# MainBoard.net
KiCad netlist of a schematic drawn in EAGLE
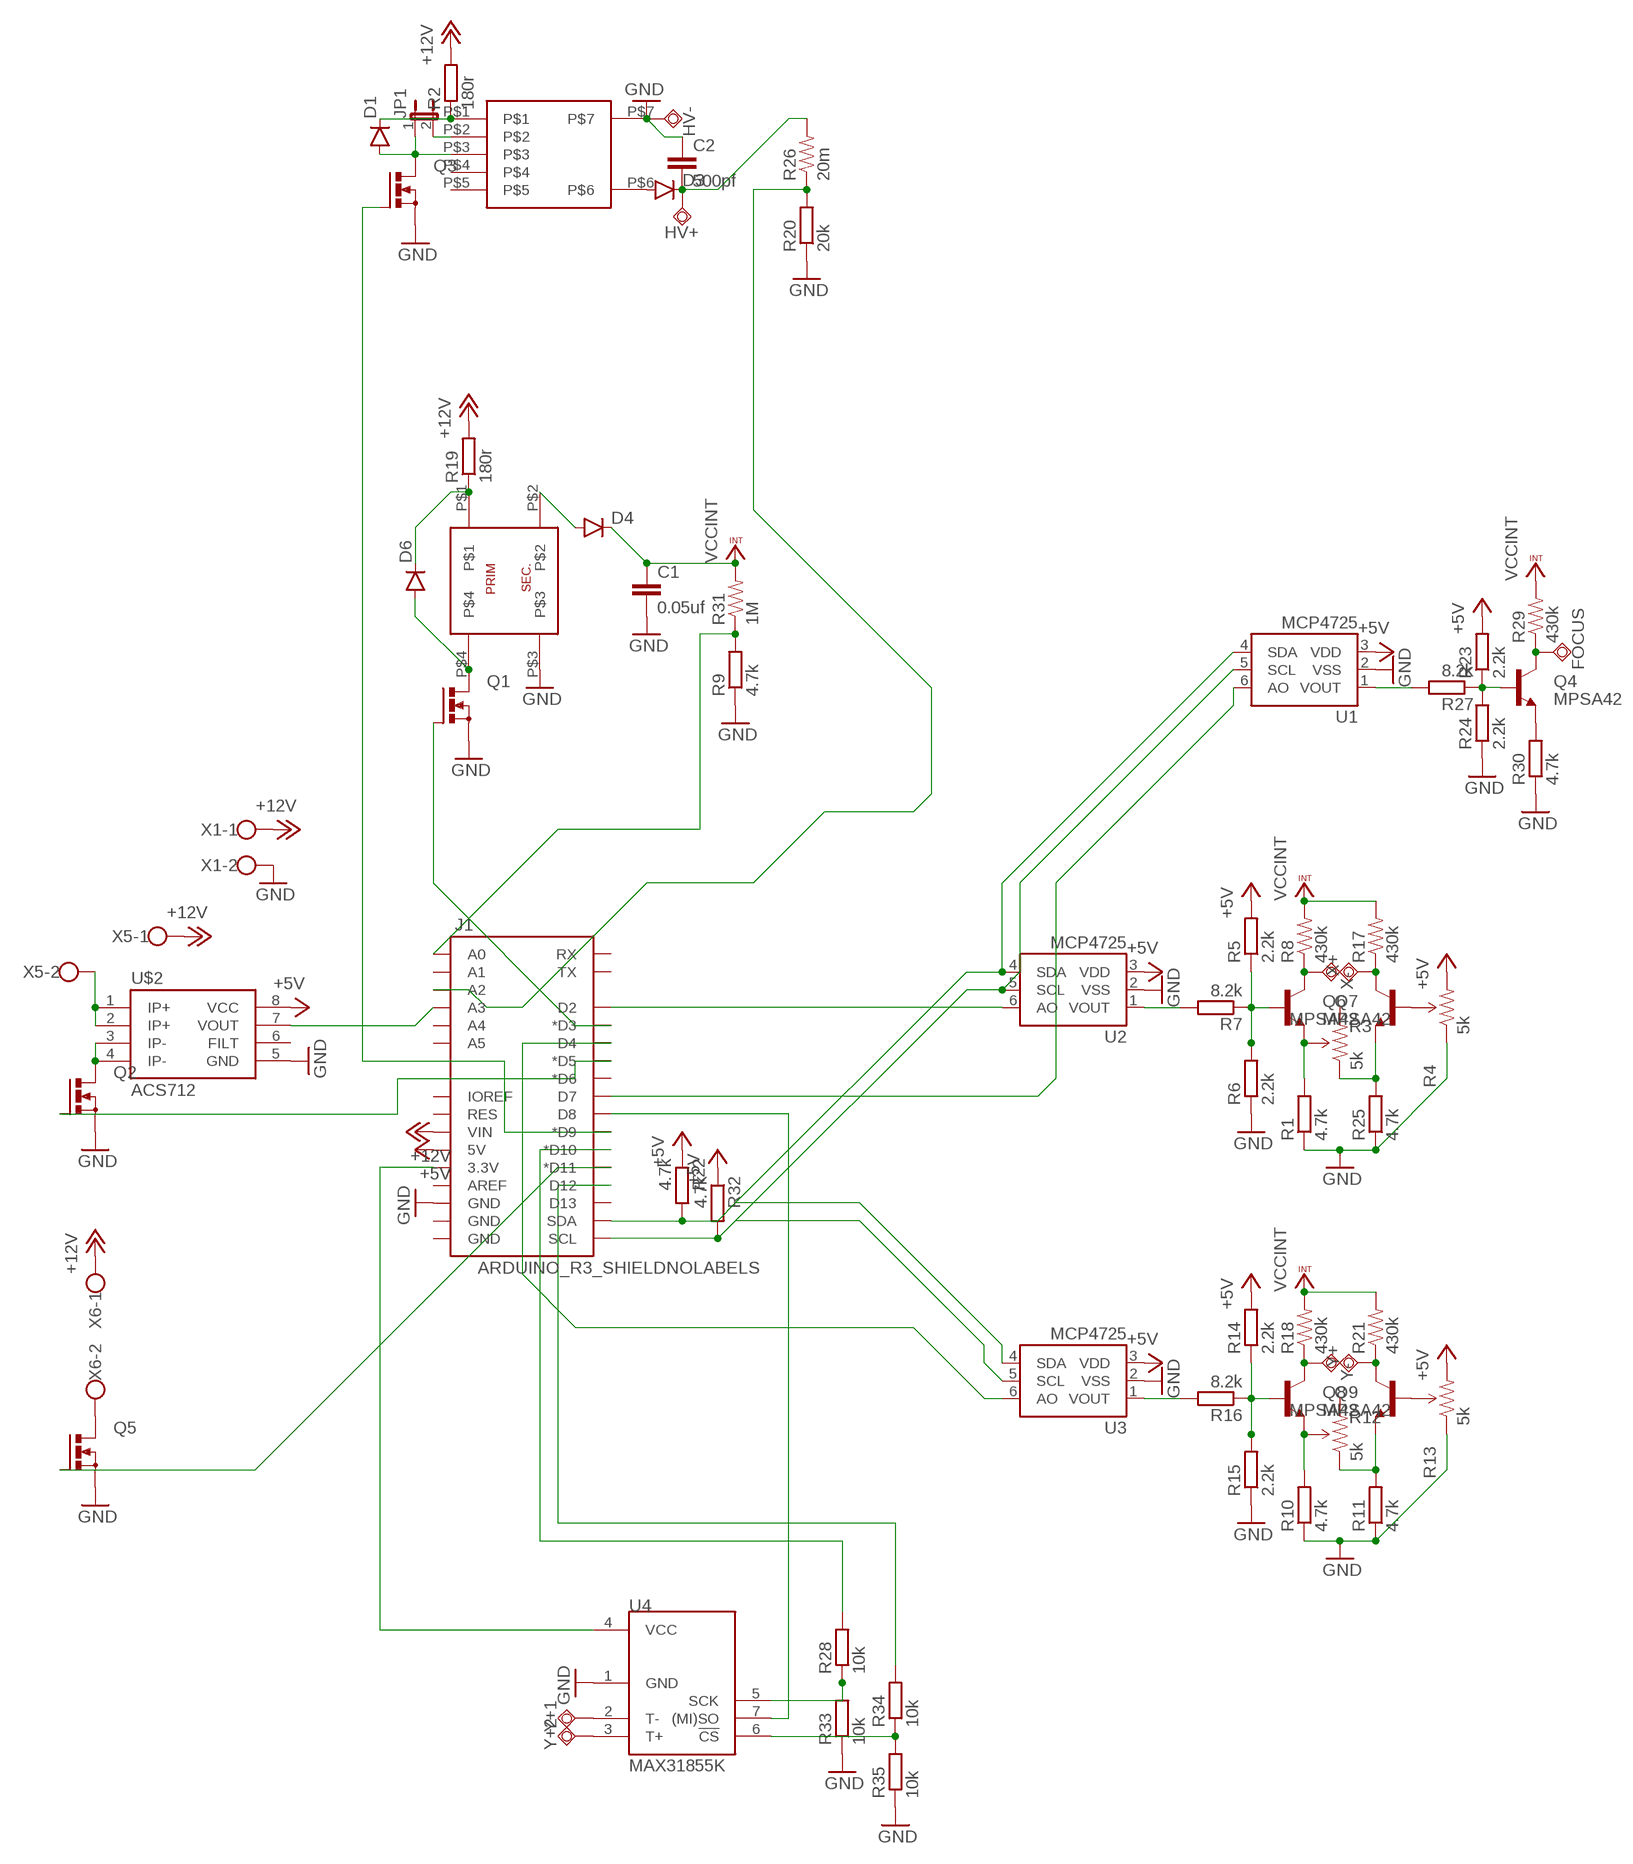
[diagram p0: schematic, sheet 1]

(export (version "E")
  (design (tool "Eeschema 10.0.6"))
  (components
    (comp (ref "C1")
      (value "0.05uf")
      (footprint "eagle-import:C1206")
      (libsource (lib "eagle-import") (part "CC1206"))
    )
    (comp (ref "C2")
      (value "500pf")
      (footprint "eagle-import:C1206")
      (libsource (lib "eagle-import") (part "CC1206"))
    )
    (comp (ref "D1")
      (value "DIODESOD123")
      (footprint "eagle-import:SOD-123")
      (libsource (lib "eagle-import") (part "DIODESOD123"))
    )
    (comp (ref "D3")
      (value "DIODEPTH")
      (footprint "eagle-import:DIODE-1N4001")
      (libsource (lib "eagle-import") (part "DIODEPTH"))
    )
    (comp (ref "D4")
      (value "DIODESOD123")
      (footprint "eagle-import:SOD-123")
      (libsource (lib "eagle-import") (part "DIODESOD123"))
    )
    (comp (ref "D6")
      (value "DIODESOD123")
      (footprint "eagle-import:SOD-123")
      (libsource (lib "eagle-import") (part "DIODESOD123"))
    )
    (comp (ref "FOCUS")
      (value "FOCUS")
      (footprint "eagle-import:P1-13")
      (libsource (lib "eagle-import") (part "TPSQPAD1-13"))
    )
    (comp (ref "HV+")
      (value "TPSQPAD1-13")
      (footprint "eagle-import:P1-13")
      (libsource (lib "eagle-import") (part "TPSQPAD1-13"))
    )
    (comp (ref "HV-")
      (value "TPSQPAD1-13")
      (footprint "eagle-import:P1-13")
      (libsource (lib "eagle-import") (part "TPSQPAD1-13"))
    )
    (comp (ref "J1")
      (value "ARDUINO_R3_SHIELDNOLABELS")
      (footprint "eagle-import:UNO_R3_SHIELD_NOLABELS")
      (libsource (lib "eagle-import") (part "ARDUINO_R3_SHIELDNOLABELS"))
    )
    (comp (ref "JP1")
      (value "JUMPER-2SMD-NO")
      (footprint "eagle-import:SJ_2S-NO")
      (libsource (lib "eagle-import") (part "JUMPER-2SMD-NO"))
    )
    (comp (ref "Q1")
      (value "N-MOSFET-SO8S")
      (footprint "eagle-import:SO-08")
      (libsource (lib "eagle-import") (part "N-MOSFET-SO8S"))
    )
    (comp (ref "Q2")
      (value "N-MOSFET-SO8S")
      (footprint "eagle-import:SO-08")
      (libsource (lib "eagle-import") (part "N-MOSFET-SO8S"))
    )
    (comp (ref "Q3")
      (value "N-MOSFET-SO8S")
      (footprint "eagle-import:SO-08")
      (libsource (lib "eagle-import") (part "N-MOSFET-SO8S"))
    )
    (comp (ref "Q4")
      (value "MPSA42")
      (footprint "eagle-import:SOT23-3")
      (libsource (lib "eagle-import") (part "TRANSISTOR_NPNMPSA42"))
    )
    (comp (ref "Q5")
      (value "N-MOSFET-SO8S")
      (footprint "eagle-import:SO-08")
      (libsource (lib "eagle-import") (part "N-MOSFET-SO8S"))
    )
    (comp (ref "Q6")
      (value "MPSA42")
      (footprint "eagle-import:SOT23-3")
      (libsource (lib "eagle-import") (part "TRANSISTOR_NPNMPSA42"))
    )
    (comp (ref "Q7")
      (value "MPSA42")
      (footprint "eagle-import:SOT23-3")
      (libsource (lib "eagle-import") (part "TRANSISTOR_NPNMPSA42"))
    )
    (comp (ref "Q8")
      (value "MPSA42")
      (footprint "eagle-import:SOT23-3")
      (libsource (lib "eagle-import") (part "TRANSISTOR_NPNMPSA42"))
    )
    (comp (ref "Q9")
      (value "MPSA42")
      (footprint "eagle-import:SOT23-3")
      (libsource (lib "eagle-import") (part "TRANSISTOR_NPNMPSA42"))
    )
    (comp (ref "R1")
      (value "4.7k")
      (footprint "eagle-import:R0603")
      (libsource (lib "eagle-import") (part "R-EU_R0603"))
    )
    (comp (ref "R2")
      (value "180r")
      (footprint "eagle-import:R0603")
      (libsource (lib "eagle-import") (part "R-EU_R0603"))
    )
    (comp (ref "R3")
      (value "5k")
      (footprint "eagle-import:TRIMPOT_PTH_S3_LOCK")
      (libsource (lib "eagle-import") (part "TRIMPOTTRIMPOT_PTH_S3_LOCK"))
    )
    (comp (ref "R4")
      (value "5k")
      (footprint "eagle-import:TRIMPOT_PTH_S3_LOCK")
      (libsource (lib "eagle-import") (part "TRIMPOTTRIMPOT_PTH_S3_LOCK"))
    )
    (comp (ref "R5")
      (value "2.2k")
      (footprint "eagle-import:R0603")
      (libsource (lib "eagle-import") (part "R-EU_R0603"))
    )
    (comp (ref "R6")
      (value "2.2k")
      (footprint "eagle-import:R0603")
      (libsource (lib "eagle-import") (part "R-EU_R0603"))
    )
    (comp (ref "R7")
      (value "8.2k")
      (footprint "eagle-import:R0603")
      (libsource (lib "eagle-import") (part "R-EU_R0603"))
    )
    (comp (ref "R8")
      (value "430k")
      (footprint "eagle-import:1206")
      (libsource (lib "eagle-import") (part "RESISTOR1206"))
    )
    (comp (ref "R9")
      (value "4.7k")
      (footprint "eagle-import:R0603")
      (libsource (lib "eagle-import") (part "R-EU_R0603"))
    )
    (comp (ref "R10")
      (value "4.7k")
      (footprint "eagle-import:R0603")
      (libsource (lib "eagle-import") (part "R-EU_R0603"))
    )
    (comp (ref "R11")
      (value "4.7k")
      (footprint "eagle-import:R0603")
      (libsource (lib "eagle-import") (part "R-EU_R0603"))
    )
    (comp (ref "R12")
      (value "5k")
      (footprint "eagle-import:TRIMPOT_PTH_S3_LOCK")
      (libsource (lib "eagle-import") (part "TRIMPOTTRIMPOT_PTH_S3_LOCK"))
    )
    (comp (ref "R13")
      (value "5k")
      (footprint "eagle-import:TRIMPOT_PTH_S3_LOCK")
      (libsource (lib "eagle-import") (part "TRIMPOTTRIMPOT_PTH_S3_LOCK"))
    )
    (comp (ref "R14")
      (value "2.2k")
      (footprint "eagle-import:R0603")
      (libsource (lib "eagle-import") (part "R-EU_R0603"))
    )
    (comp (ref "R15")
      (value "2.2k")
      (footprint "eagle-import:R0603")
      (libsource (lib "eagle-import") (part "R-EU_R0603"))
    )
    (comp (ref "R16")
      (value "8.2k")
      (footprint "eagle-import:R0603")
      (libsource (lib "eagle-import") (part "R-EU_R0603"))
    )
    (comp (ref "R17")
      (value "430k")
      (footprint "eagle-import:1206")
      (libsource (lib "eagle-import") (part "RESISTOR1206"))
    )
    (comp (ref "R18")
      (value "430k")
      (footprint "eagle-import:1206")
      (libsource (lib "eagle-import") (part "RESISTOR1206"))
    )
    (comp (ref "R19")
      (value "180r")
      (footprint "eagle-import:R0603")
      (libsource (lib "eagle-import") (part "R-EU_R0603"))
    )
    (comp (ref "R20")
      (value "20k")
      (footprint "eagle-import:R0603")
      (libsource (lib "eagle-import") (part "R-EU_R0603"))
    )
    (comp (ref "R21")
      (value "430k")
      (footprint "eagle-import:1206")
      (libsource (lib "eagle-import") (part "RESISTOR1206"))
    )
    (comp (ref "R22")
      (value "4.7k")
      (footprint "eagle-import:R0603")
      (libsource (lib "eagle-import") (part "R-EU_R0603"))
    )
    (comp (ref "R23")
      (value "2.2k")
      (footprint "eagle-import:R0603")
      (libsource (lib "eagle-import") (part "R-EU_R0603"))
    )
    (comp (ref "R24")
      (value "2.2k")
      (footprint "eagle-import:R0603")
      (libsource (lib "eagle-import") (part "R-EU_R0603"))
    )
    (comp (ref "R25")
      (value "4.7k")
      (footprint "eagle-import:R0603")
      (libsource (lib "eagle-import") (part "R-EU_R0603"))
    )
    (comp (ref "R26")
      (value "20m")
      (footprint "eagle-import:AXIAL-0.4")
      (libsource (lib "eagle-import") (part "RESISTORPTH-1/4W"))
    )
    (comp (ref "R27")
      (value "8.2k")
      (footprint "eagle-import:R0603")
      (libsource (lib "eagle-import") (part "R-EU_R0603"))
    )
    (comp (ref "R28")
      (value "10k")
      (footprint "eagle-import:R0603")
      (libsource (lib "eagle-import") (part "R-EU_R0603"))
    )
    (comp (ref "R29")
      (value "430k")
      (footprint "eagle-import:1206")
      (libsource (lib "eagle-import") (part "RESISTOR1206"))
    )
    (comp (ref "R30")
      (value "4.7k")
      (footprint "eagle-import:R0603")
      (libsource (lib "eagle-import") (part "R-EU_R0603"))
    )
    (comp (ref "R31")
      (value "1M")
      (footprint "eagle-import:1206")
      (libsource (lib "eagle-import") (part "RESISTOR1206"))
    )
    (comp (ref "R32")
      (value "4.7k")
      (footprint "eagle-import:R0603")
      (libsource (lib "eagle-import") (part "R-EU_R0603"))
    )
    (comp (ref "R33")
      (value "10k")
      (footprint "eagle-import:R0603")
      (libsource (lib "eagle-import") (part "R-EU_R0603"))
    )
    (comp (ref "R34")
      (value "10k")
      (footprint "eagle-import:R0603")
      (libsource (lib "eagle-import") (part "R-EU_R0603"))
    )
    (comp (ref "R35")
      (value "10k")
      (footprint "eagle-import:R0603")
      (libsource (lib "eagle-import") (part "R-EU_R0603"))
    )
    (comp (ref "U$1")
      (value "ATB")
      (footprint "eagle-import:ATB3225")
      (libsource (lib "eagle-import") (part "ATB"))
    )
    (comp (ref "U$2")
      (value "ACS712")
      (footprint "eagle-import:SO08")
      (libsource (lib "eagle-import") (part "ACS712"))
    )
    (comp (ref "U$3")
      (value "CTX")
      (footprint "eagle-import:CTX")
      (libsource (lib "eagle-import") (part "CTX"))
    )
    (comp (ref "U1")
      (value "MCP4725")
      (footprint "eagle-import:SOT23-6")
      (libsource (lib "eagle-import") (part "MCP4725SOT-23"))
    )
    (comp (ref "U2")
      (value "MCP4725")
      (footprint "eagle-import:SOT23-6")
      (libsource (lib "eagle-import") (part "MCP4725SOT-23"))
    )
    (comp (ref "U3")
      (value "MCP4725")
      (footprint "eagle-import:SOT23-6")
      (libsource (lib "eagle-import") (part "MCP4725SOT-23"))
    )
    (comp (ref "U4")
      (value "MAX31855K")
      (footprint "eagle-import:SOIC8")
      (libsource (lib "eagle-import") (part "MAX31855K"))
    )
    (comp (ref "X+")
      (value "TPSQPAD1-13")
      (footprint "eagle-import:P1-13")
      (libsource (lib "eagle-import") (part "TPSQPAD1-13"))
    )
    (comp (ref "X-")
      (value "TPSQPAD1-13")
      (footprint "eagle-import:P1-13")
      (libsource (lib "eagle-import") (part "TPSQPAD1-13"))
    )
    (comp (ref "X1")
      (value "W237-102")
      (footprint "eagle-import:W237-102")
      (fields (field (name "MPN") "237-102"))
      (libsource (lib "eagle-import") (part "W237-102"))
    )
    (comp (ref "X5")
      (value "W237-102")
      (footprint "eagle-import:W237-102")
      (fields (field (name "MPN") "237-102"))
      (libsource (lib "eagle-import") (part "W237-102"))
    )
    (comp (ref "X6")
      (value "W237-102")
      (footprint "eagle-import:W237-102")
      (fields (field (name "MPN") "237-102"))
      (libsource (lib "eagle-import") (part "W237-102"))
    )
    (comp (ref "Y+")
      (value "TPSQPAD1-13")
      (footprint "eagle-import:P1-13")
      (libsource (lib "eagle-import") (part "TPSQPAD1-13"))
    )
    (comp (ref "Y+1")
      (value "TPSQPAD1-13")
      (footprint "eagle-import:P1-13")
      (libsource (lib "eagle-import") (part "TPSQPAD1-13"))
    )
    (comp (ref "Y+2")
      (value "TPSQPAD1-13")
      (footprint "eagle-import:P1-13")
      (libsource (lib "eagle-import") (part "TPSQPAD1-13"))
    )
    (comp (ref "Y-")
      (value "TPSQPAD1-13")
      (footprint "eagle-import:P1-13")
      (libsource (lib "eagle-import") (part "TPSQPAD1-13"))
    )
  )
  (nets
    (net (code "1") (name "+5V") (class "Default")
      (node (ref "J1") (pin "5V") (pinfunction "5V_5V") (pintype "bidirectional"))
      (node (ref "R13") (pin "3") (pinfunction "CW_3") (pintype "passive"))
      (node (ref "R14") (pin "2") (pinfunction "2_2") (pintype "passive"))
      (node (ref "R22") (pin "1") (pinfunction "1_1") (pintype "passive"))
      (node (ref "R23") (pin "2") (pinfunction "2_2") (pintype "passive"))
      (node (ref "R32") (pin "1") (pinfunction "1_1") (pintype "passive"))
      (node (ref "R4") (pin "3") (pinfunction "CW_3") (pintype "passive"))
      (node (ref "R5") (pin "2") (pinfunction "2_2") (pintype "passive"))
      (node (ref "U$2") (pin "8") (pinfunction "VCC_8") (pintype "bidirectional"))
      (node (ref "U1") (pin "3") (pinfunction "VDD_3") (pintype "bidirectional"))
      (node (ref "U2") (pin "3") (pinfunction "VDD_3") (pintype "bidirectional"))
      (node (ref "U3") (pin "3") (pinfunction "VDD_3") (pintype "bidirectional"))
    )
    (net (code "2") (name "+12V") (class "Default")
      (node (ref "J1") (pin "VIN") (pinfunction "VIN_VIN") (pintype "bidirectional"))
      (node (ref "R19") (pin "2") (pinfunction "2_2") (pintype "passive"))
      (node (ref "R2") (pin "2") (pinfunction "2_2") (pintype "passive"))
      (node (ref "X1") (pin "1") (pinfunction "KL_1") (pintype "passive"))
      (node (ref "X5") (pin "1") (pinfunction "KL_1") (pintype "passive"))
      (node (ref "X6") (pin "1") (pinfunction "KL_1") (pintype "passive"))
    )
    (net (code "3") (name "GND") (class "Default")
      (node (ref "C1") (pin "2") (pinfunction "2_2") (pintype "passive"))
      (node (ref "C2") (pin "1") (pinfunction "1_1") (pintype "passive"))
      (node (ref "HV-") (pin "TP") (pinfunction "TP_TP") (pintype "input"))
      (node (ref "J1") (pin "GND@2") (pinfunction "GND_GND@2") (pintype "bidirectional"))
      (node (ref "Q1") (pin "1") (pinfunction "S_1") (pintype "passive"))
      (node (ref "Q1") (pin "2") (pinfunction "S_2") (pintype "passive"))
      (node (ref "Q1") (pin "3") (pinfunction "S_3") (pintype "passive"))
      (node (ref "Q2") (pin "1") (pinfunction "S_1") (pintype "passive"))
      (node (ref "Q2") (pin "2") (pinfunction "S_2") (pintype "passive"))
      (node (ref "Q2") (pin "3") (pinfunction "S_3") (pintype "passive"))
      (node (ref "Q3") (pin "1") (pinfunction "S_1") (pintype "passive"))
      (node (ref "Q3") (pin "2") (pinfunction "S_2") (pintype "passive"))
      (node (ref "Q3") (pin "3") (pinfunction "S_3") (pintype "passive"))
      (node (ref "Q5") (pin "1") (pinfunction "S_1") (pintype "passive"))
      (node (ref "Q5") (pin "2") (pinfunction "S_2") (pintype "passive"))
      (node (ref "Q5") (pin "3") (pinfunction "S_3") (pintype "passive"))
      (node (ref "R1") (pin "1") (pinfunction "1_1") (pintype "passive"))
      (node (ref "R10") (pin "1") (pinfunction "1_1") (pintype "passive"))
      (node (ref "R11") (pin "1") (pinfunction "1_1") (pintype "passive"))
      (node (ref "R13") (pin "1") (pinfunction "CCW_1") (pintype "passive"))
      (node (ref "R15") (pin "1") (pinfunction "1_1") (pintype "passive"))
      (node (ref "R20") (pin "1") (pinfunction "1_1") (pintype "passive"))
      (node (ref "R24") (pin "1") (pinfunction "1_1") (pintype "passive"))
      (node (ref "R25") (pin "1") (pinfunction "1_1") (pintype "passive"))
      (node (ref "R30") (pin "1") (pinfunction "1_1") (pintype "passive"))
      (node (ref "R33") (pin "1") (pinfunction "1_1") (pintype "passive"))
      (node (ref "R35") (pin "1") (pinfunction "1_1") (pintype "passive"))
      (node (ref "R4") (pin "1") (pinfunction "CCW_1") (pintype "passive"))
      (node (ref "R6") (pin "1") (pinfunction "1_1") (pintype "passive"))
      (node (ref "R9") (pin "1") (pinfunction "1_1") (pintype "passive"))
      (node (ref "U$1") (pin "P$3") (pinfunction "P$3_P$3") (pintype "bidirectional"))
      (node (ref "U$2") (pin "5") (pinfunction "GND_5") (pintype "bidirectional"))
      (node (ref "U$3") (pin "P$7") (pinfunction "P$7_P$7") (pintype "bidirectional"))
      (node (ref "U1") (pin "2") (pinfunction "VSS_2") (pintype "bidirectional"))
      (node (ref "U2") (pin "2") (pinfunction "VSS_2") (pintype "bidirectional"))
      (node (ref "U3") (pin "2") (pinfunction "VSS_2") (pintype "bidirectional"))
      (node (ref "U4") (pin "1") (pinfunction "GND_1") (pintype "bidirectional"))
      (node (ref "X1") (pin "2") (pinfunction "KL_2") (pintype "passive"))
    )
    (net (code "4") (name "Net-(D1-PadA)") (class "Default")
      (node (ref "D1") (pin "A") (pinfunction "A_A") (pintype "passive"))
      (node (ref "JP1") (pin "1") (pinfunction "1_1") (pintype "passive"))
      (node (ref "Q3") (pin "5") (pinfunction "D_5") (pintype "passive"))
      (node (ref "Q3") (pin "6") (pinfunction "D_6") (pintype "passive"))
      (node (ref "Q3") (pin "7") (pinfunction "D_7") (pintype "passive"))
      (node (ref "Q3") (pin "8") (pinfunction "D_8") (pintype "passive"))
      (node (ref "U$3") (pin "P$3") (pinfunction "P$3_P$3") (pintype "bidirectional"))
    )
    (net (code "5") (name "Net-(D1-PadC)") (class "Default")
      (node (ref "D1") (pin "C") (pinfunction "C_C") (pintype "passive"))
      (node (ref "R2") (pin "1") (pinfunction "1_1") (pintype "passive"))
      (node (ref "U$3") (pin "P$1") (pinfunction "P$1_P$1") (pintype "bidirectional"))
    )
    (net (code "6") (name "Net-(D3-PadA)") (class "Default")
      (node (ref "D3") (pin "A") (pinfunction "A_A") (pintype "passive"))
      (node (ref "U$3") (pin "P$6") (pinfunction "P$6_P$6") (pintype "bidirectional"))
    )
    (net (code "7") (name "Net-(D4-PadA)") (class "Default")
      (node (ref "D4") (pin "A") (pinfunction "A_A") (pintype "passive"))
      (node (ref "U$1") (pin "P$2") (pinfunction "P$2_P$2") (pintype "bidirectional"))
    )
    (net (code "8") (name "Net-(D6-PadA)") (class "Default")
      (node (ref "D6") (pin "A") (pinfunction "A_A") (pintype "passive"))
      (node (ref "Q1") (pin "5") (pinfunction "D_5") (pintype "passive"))
      (node (ref "Q1") (pin "6") (pinfunction "D_6") (pintype "passive"))
      (node (ref "Q1") (pin "7") (pinfunction "D_7") (pintype "passive"))
      (node (ref "Q1") (pin "8") (pinfunction "D_8") (pintype "passive"))
      (node (ref "U$1") (pin "P$4") (pinfunction "P$4_P$4") (pintype "bidirectional"))
    )
    (net (code "9") (name "Net-(D6-PadC)") (class "Default")
      (node (ref "D6") (pin "C") (pinfunction "C_C") (pintype "passive"))
      (node (ref "R19") (pin "1") (pinfunction "1_1") (pintype "passive"))
      (node (ref "U$1") (pin "P$1") (pinfunction "P$1_P$1") (pintype "bidirectional"))
    )
    (net (code "10") (name "Net-(J1-*D3)") (class "Default")
      (node (ref "J1") (pin "D3") (pinfunction "*D3_D3") (pintype "bidirectional"))
      (node (ref "Q1") (pin "4") (pinfunction "G_4") (pintype "passive"))
    )
    (net (code "11") (name "Net-(J1-*D5)") (class "Default")
      (node (ref "J1") (pin "D5") (pinfunction "*D5_D5") (pintype "bidirectional"))
      (node (ref "Q2") (pin "4") (pinfunction "G_4") (pintype "passive"))
    )
    (net (code "12") (name "Net-(J1-*D9)") (class "Default")
      (node (ref "J1") (pin "D9") (pinfunction "*D9_D9") (pintype "bidirectional"))
      (node (ref "Q3") (pin "4") (pinfunction "G_4") (pintype "passive"))
    )
    (net (code "13") (name "Net-(J1-*D10)") (class "Default")
      (node (ref "J1") (pin "D10") (pinfunction "*D10_D10") (pintype "bidirectional"))
      (node (ref "R28") (pin "2") (pinfunction "2_2") (pintype "passive"))
    )
    (net (code "14") (name "Net-(J1-*D11)") (class "Default")
      (node (ref "J1") (pin "D11") (pinfunction "*D11_D11") (pintype "bidirectional"))
      (node (ref "Q5") (pin "4") (pinfunction "G_4") (pintype "passive"))
    )
    (net (code "15") (name "Net-(J1-PadA0)") (class "Default")
      (node (ref "J1") (pin "A0") (pinfunction "A0_A0") (pintype "bidirectional"))
      (node (ref "R31") (pin "1") (pinfunction "1_1") (pintype "passive"))
      (node (ref "R9") (pin "2") (pinfunction "2_2") (pintype "passive"))
    )
    (net (code "16") (name "Net-(J1-PadD12)") (class "Default")
      (node (ref "J1") (pin "D12") (pinfunction "D12_D12") (pintype "bidirectional"))
      (node (ref "R34") (pin "2") (pinfunction "2_2") (pintype "passive"))
    )
    (net (code "17") (name "Net-(JP1-Pad2)") (class "Default")
      (node (ref "JP1") (pin "2") (pinfunction "2_2") (pintype "passive"))
      (node (ref "U$3") (pin "P$2") (pinfunction "P$2_P$2") (pintype "bidirectional"))
    )
    (net (code "18") (name "Net-(Q2-D-Pad5)") (class "Default")
      (node (ref "Q2") (pin "5") (pinfunction "D_5") (pintype "passive"))
      (node (ref "Q2") (pin "6") (pinfunction "D_6") (pintype "passive"))
      (node (ref "Q2") (pin "7") (pinfunction "D_7") (pintype "passive"))
      (node (ref "Q2") (pin "8") (pinfunction "D_8") (pintype "passive"))
      (node (ref "U$2") (pin "3") (pinfunction "IP-_3") (pintype "bidirectional"))
      (node (ref "U$2") (pin "4") (pinfunction "IP-_4") (pintype "bidirectional"))
    )
    (net (code "19") (name "Net-(Q4-B)") (class "Default")
      (node (ref "Q4") (pin "1") (pinfunction "B_1") (pintype "passive"))
      (node (ref "R23") (pin "1") (pinfunction "1_1") (pintype "passive"))
      (node (ref "R24") (pin "2") (pinfunction "2_2") (pintype "passive"))
      (node (ref "R27") (pin "1") (pinfunction "1_1") (pintype "passive"))
    )
    (net (code "20") (name "Net-(Q4-C)") (class "Default")
      (node (ref "FOCUS") (pin "TP") (pinfunction "TP_TP") (pintype "input"))
      (node (ref "Q4") (pin "3") (pinfunction "C_3") (pintype "passive"))
      (node (ref "R29") (pin "1") (pinfunction "1_1") (pintype "passive"))
    )
    (net (code "21") (name "Net-(Q4-E)") (class "Default")
      (node (ref "Q4") (pin "2") (pinfunction "E_2") (pintype "passive"))
      (node (ref "R30") (pin "2") (pinfunction "2_2") (pintype "passive"))
    )
    (net (code "22") (name "Net-(Q6-B)") (class "Default")
      (node (ref "Q6") (pin "1") (pinfunction "B_1") (pintype "passive"))
      (node (ref "R5") (pin "1") (pinfunction "1_1") (pintype "passive"))
      (node (ref "R6") (pin "2") (pinfunction "2_2") (pintype "passive"))
      (node (ref "R7") (pin "1") (pinfunction "1_1") (pintype "passive"))
    )
    (net (code "23") (name "Net-(Q6-C)") (class "Default")
      (node (ref "Q6") (pin "3") (pinfunction "C_3") (pintype "passive"))
      (node (ref "R8") (pin "1") (pinfunction "1_1") (pintype "passive"))
      (node (ref "X-") (pin "TP") (pinfunction "TP_TP") (pintype "input"))
    )
    (net (code "24") (name "Net-(Q6-E)") (class "Default")
      (node (ref "Q6") (pin "2") (pinfunction "E_2") (pintype "passive"))
      (node (ref "R1") (pin "2") (pinfunction "2_2") (pintype "passive"))
      (node (ref "R3") (pin "2") (pinfunction "WIPER_2") (pintype "passive"))
    )
    (net (code "25") (name "Net-(Q7-B)") (class "Default")
      (node (ref "Q7") (pin "1") (pinfunction "B_1") (pintype "passive"))
      (node (ref "R4") (pin "2") (pinfunction "WIPER_2") (pintype "passive"))
    )
    (net (code "26") (name "Net-(Q7-C)") (class "Default")
      (node (ref "Q7") (pin "3") (pinfunction "C_3") (pintype "passive"))
      (node (ref "R17") (pin "1") (pinfunction "1_1") (pintype "passive"))
      (node (ref "X+") (pin "TP") (pinfunction "TP_TP") (pintype "input"))
    )
    (net (code "27") (name "Net-(Q7-E)") (class "Default")
      (node (ref "Q7") (pin "2") (pinfunction "E_2") (pintype "passive"))
      (node (ref "R25") (pin "2") (pinfunction "2_2") (pintype "passive"))
      (node (ref "R3") (pin "1") (pinfunction "CCW_1") (pintype "passive"))
    )
    (net (code "28") (name "Net-(Q8-B)") (class "Default")
      (node (ref "Q8") (pin "1") (pinfunction "B_1") (pintype "passive"))
      (node (ref "R14") (pin "1") (pinfunction "1_1") (pintype "passive"))
      (node (ref "R15") (pin "2") (pinfunction "2_2") (pintype "passive"))
      (node (ref "R16") (pin "1") (pinfunction "1_1") (pintype "passive"))
    )
    (net (code "29") (name "Net-(Q8-C)") (class "Default")
      (node (ref "Q8") (pin "3") (pinfunction "C_3") (pintype "passive"))
      (node (ref "R18") (pin "1") (pinfunction "1_1") (pintype "passive"))
      (node (ref "Y-") (pin "TP") (pinfunction "TP_TP") (pintype "input"))
    )
    (net (code "30") (name "Net-(Q8-E)") (class "Default")
      (node (ref "Q8") (pin "2") (pinfunction "E_2") (pintype "passive"))
      (node (ref "R10") (pin "2") (pinfunction "2_2") (pintype "passive"))
      (node (ref "R12") (pin "2") (pinfunction "WIPER_2") (pintype "passive"))
    )
    (net (code "31") (name "Net-(Q9-B)") (class "Default")
      (node (ref "Q9") (pin "1") (pinfunction "B_1") (pintype "passive"))
      (node (ref "R13") (pin "2") (pinfunction "WIPER_2") (pintype "passive"))
    )
    (net (code "32") (name "Net-(Q9-C)") (class "Default")
      (node (ref "Q9") (pin "3") (pinfunction "C_3") (pintype "passive"))
      (node (ref "R21") (pin "1") (pinfunction "1_1") (pintype "passive"))
      (node (ref "Y+") (pin "TP") (pinfunction "TP_TP") (pintype "input"))
    )
    (net (code "33") (name "Net-(Q9-E)") (class "Default")
      (node (ref "Q9") (pin "2") (pinfunction "E_2") (pintype "passive"))
      (node (ref "R11") (pin "2") (pinfunction "2_2") (pintype "passive"))
      (node (ref "R12") (pin "1") (pinfunction "CCW_1") (pintype "passive"))
    )
    (net (code "34") (name "Net-(R26-1)") (class "Default")
      (node (ref "J1") (pin "A2") (pinfunction "A2_A2") (pintype "bidirectional"))
      (node (ref "R20") (pin "2") (pinfunction "2_2") (pintype "passive"))
      (node (ref "R26") (pin "P$1") (pinfunction "1_P$1") (pintype "passive"))
    )
    (net (code "35") (name "Net-(R26-2)") (class "Default")
      (node (ref "C2") (pin "2") (pinfunction "2_2") (pintype "passive"))
      (node (ref "D3") (pin "C") (pinfunction "C_C") (pintype "passive"))
      (node (ref "HV+") (pin "TP") (pinfunction "TP_TP") (pintype "input"))
      (node (ref "R26") (pin "P$2") (pinfunction "2_P$2") (pintype "passive"))
    )
    (net (code "36") (name "Net-(U$2-VOUT)") (class "Default")
      (node (ref "J1") (pin "A3") (pinfunction "A3_A3") (pintype "bidirectional"))
      (node (ref "U$2") (pin "7") (pinfunction "VOUT_7") (pintype "bidirectional"))
    )
    (net (code "37") (name "Net-(U1-AO)") (class "Default")
      (node (ref "J1") (pin "D7") (pinfunction "D7_D7") (pintype "bidirectional"))
      (node (ref "U1") (pin "6") (pinfunction "AO_6") (pintype "bidirectional"))
    )
    (net (code "38") (name "Net-(U1-SCL)") (class "Default")
      (node (ref "J1") (pin "SCL") (pinfunction "SCL_SCL") (pintype "bidirectional"))
      (node (ref "R32") (pin "2") (pinfunction "2_2") (pintype "passive"))
      (node (ref "U1") (pin "5") (pinfunction "SCL_5") (pintype "bidirectional"))
      (node (ref "U2") (pin "5") (pinfunction "SCL_5") (pintype "bidirectional"))
      (node (ref "U3") (pin "5") (pinfunction "SCL_5") (pintype "bidirectional"))
    )
    (net (code "39") (name "Net-(U1-SDA)") (class "Default")
      (node (ref "J1") (pin "SDA") (pinfunction "SDA_SDA") (pintype "bidirectional"))
      (node (ref "R22") (pin "2") (pinfunction "2_2") (pintype "passive"))
      (node (ref "U1") (pin "4") (pinfunction "SDA_4") (pintype "bidirectional"))
      (node (ref "U2") (pin "4") (pinfunction "SDA_4") (pintype "bidirectional"))
      (node (ref "U3") (pin "4") (pinfunction "SDA_4") (pintype "bidirectional"))
    )
    (net (code "40") (name "Net-(U1-VOUT)") (class "Default")
      (node (ref "R27") (pin "2") (pinfunction "2_2") (pintype "passive"))
      (node (ref "U1") (pin "1") (pinfunction "VOUT_1") (pintype "bidirectional"))
    )
    (net (code "41") (name "Net-(U2-AO)") (class "Default")
      (node (ref "J1") (pin "D2") (pinfunction "D2_D2") (pintype "bidirectional"))
      (node (ref "U2") (pin "6") (pinfunction "AO_6") (pintype "bidirectional"))
    )
    (net (code "42") (name "Net-(U2-VOUT)") (class "Default")
      (node (ref "R7") (pin "2") (pinfunction "2_2") (pintype "passive"))
      (node (ref "U2") (pin "1") (pinfunction "VOUT_1") (pintype "bidirectional"))
    )
    (net (code "43") (name "Net-(U3-AO)") (class "Default")
      (node (ref "J1") (pin "D4") (pinfunction "D4_D4") (pintype "bidirectional"))
      (node (ref "U3") (pin "6") (pinfunction "AO_6") (pintype "bidirectional"))
    )
    (net (code "44") (name "Net-(U3-VOUT)") (class "Default")
      (node (ref "R16") (pin "2") (pinfunction "2_2") (pintype "passive"))
      (node (ref "U3") (pin "1") (pinfunction "VOUT_1") (pintype "bidirectional"))
    )
    (net (code "45") (name "Net-(U4-(MI)SO)") (class "Default")
      (node (ref "J1") (pin "D8") (pinfunction "D8_D8") (pintype "bidirectional"))
      (node (ref "U4") (pin "7") (pinfunction "(MI)SO_7") (pintype "bidirectional"))
    )
    (net (code "46") (name "Net-(U4-SCK)") (class "Default")
      (node (ref "R28") (pin "1") (pinfunction "1_1") (pintype "passive"))
      (node (ref "R33") (pin "2") (pinfunction "2_2") (pintype "passive"))
      (node (ref "U4") (pin "5") (pinfunction "SCK_5") (pintype "bidirectional"))
    )
    (net (code "47") (name "Net-(U4-T+)") (class "Default")
      (node (ref "U4") (pin "3") (pinfunction "T+_3") (pintype "bidirectional"))
      (node (ref "Y+2") (pin "TP") (pinfunction "TP_TP") (pintype "input"))
    )
    (net (code "48") (name "Net-(U4-T-)") (class "Default")
      (node (ref "U4") (pin "2") (pinfunction "T-_2") (pintype "bidirectional"))
      (node (ref "Y+1") (pin "TP") (pinfunction "TP_TP") (pintype "input"))
    )
    (net (code "49") (name "Net-(U4-VCC)") (class "Default")
      (node (ref "J1") (pin "3.3V") (pinfunction "3.3V_3.3V") (pintype "bidirectional"))
      (node (ref "U4") (pin "4") (pinfunction "VCC_4") (pintype "bidirectional"))
    )
    (net (code "50") (name "Net-(U4-~{CS})") (class "Default")
      (node (ref "R34") (pin "1") (pinfunction "1_1") (pintype "passive"))
      (node (ref "R35") (pin "2") (pinfunction "2_2") (pintype "passive"))
      (node (ref "U4") (pin "6") (pinfunction "~{CS}_6") (pintype "bidirectional"))
    )
    (net (code "51") (name "Net-(X5B-KL)") (class "Default")
      (node (ref "U$2") (pin "1") (pinfunction "IP+_1") (pintype "bidirectional"))
      (node (ref "U$2") (pin "2") (pinfunction "IP+_2") (pintype "bidirectional"))
      (node (ref "X5") (pin "2") (pinfunction "KL_2") (pintype "passive"))
    )
    (net (code "52") (name "Net-(X6B-KL)") (class "Default")
      (node (ref "Q5") (pin "5") (pinfunction "D_5") (pintype "passive"))
      (node (ref "Q5") (pin "6") (pinfunction "D_6") (pintype "passive"))
      (node (ref "Q5") (pin "7") (pinfunction "D_7") (pintype "passive"))
      (node (ref "Q5") (pin "8") (pinfunction "D_8") (pintype "passive"))
      (node (ref "X6") (pin "2") (pinfunction "KL_2") (pintype "passive"))
    )
    (net (code "53") (name "VCCINT") (class "Default")
      (node (ref "C1") (pin "1") (pinfunction "1_1") (pintype "passive"))
      (node (ref "D4") (pin "C") (pinfunction "C_C") (pintype "passive"))
      (node (ref "R17") (pin "2") (pinfunction "2_2") (pintype "passive"))
      (node (ref "R18") (pin "2") (pinfunction "2_2") (pintype "passive"))
      (node (ref "R21") (pin "2") (pinfunction "2_2") (pintype "passive"))
      (node (ref "R29") (pin "2") (pinfunction "2_2") (pintype "passive"))
      (node (ref "R31") (pin "2") (pinfunction "2_2") (pintype "passive"))
      (node (ref "R8") (pin "2") (pinfunction "2_2") (pintype "passive"))
    )
    (net (code "54") (name "unconnected-(J1-*D6-PadD6)") (class "Default")
      (node (ref "J1") (pin "D6") (pinfunction "*D6_D6") (pintype "bidirectional"))
    )
    (net (code "55") (name "unconnected-(J1-GND-PadGND@0)") (class "Default")
      (node (ref "J1") (pin "GND@0") (pinfunction "GND_GND@0") (pintype "bidirectional"))
    )
    (net (code "56") (name "unconnected-(J1-GND-PadGND@1)") (class "Default")
      (node (ref "J1") (pin "GND@1") (pinfunction "GND_GND@1") (pintype "bidirectional"))
    )
    (net (code "57") (name "unconnected-(J1-PadA1)") (class "Default")
      (node (ref "J1") (pin "A1") (pinfunction "A1_A1") (pintype "bidirectional"))
    )
    (net (code "58") (name "unconnected-(J1-PadA4)") (class "Default")
      (node (ref "J1") (pin "A4") (pinfunction "A4_A4") (pintype "bidirectional"))
    )
    (net (code "59") (name "unconnected-(J1-PadA5)") (class "Default")
      (node (ref "J1") (pin "A5") (pinfunction "A5_A5") (pintype "bidirectional"))
    )
    (net (code "60") (name "unconnected-(J1-PadAREF)") (class "Default")
      (node (ref "J1") (pin "AREF") (pinfunction "AREF_AREF") (pintype "bidirectional"))
    )
    (net (code "61") (name "unconnected-(J1-PadD13)") (class "Default")
      (node (ref "J1") (pin "D13") (pinfunction "D13_D13") (pintype "bidirectional"))
    )
    (net (code "62") (name "unconnected-(J1-PadIOREF)") (class "Default")
      (node (ref "J1") (pin "IOREF") (pinfunction "IOREF_IOREF") (pintype "bidirectional"))
    )
    (net (code "63") (name "unconnected-(J1-PadRES)") (class "Default")
      (node (ref "J1") (pin "RES") (pinfunction "RES_RES") (pintype "bidirectional"))
    )
    (net (code "64") (name "unconnected-(J1-PadRX)") (class "Default")
      (node (ref "J1") (pin "RX") (pinfunction "RX_RX") (pintype "bidirectional"))
    )
    (net (code "65") (name "unconnected-(J1-PadTX)") (class "Default")
      (node (ref "J1") (pin "TX") (pinfunction "TX_TX") (pintype "bidirectional"))
    )
    (net (code "66") (name "unconnected-(R3-CW-Pad3)") (class "Default")
      (node (ref "R3") (pin "3") (pinfunction "CW_3") (pintype "passive"))
    )
    (net (code "67") (name "unconnected-(R12-CW-Pad3)") (class "Default")
      (node (ref "R12") (pin "3") (pinfunction "CW_3") (pintype "passive"))
    )
    (net (code "68") (name "unconnected-(U$2-FILT-Pad6)") (class "Default")
      (node (ref "U$2") (pin "6") (pinfunction "FILT_6") (pintype "bidirectional"))
    )
    (net (code "69") (name "unconnected-(U$3-PadP$4)") (class "Default")
      (node (ref "U$3") (pin "P$4") (pinfunction "P$4_P$4") (pintype "bidirectional"))
    )
    (net (code "70") (name "unconnected-(U$3-PadP$5)") (class "Default")
      (node (ref "U$3") (pin "P$5") (pinfunction "P$5_P$5") (pintype "bidirectional"))
    )
  )
)
